# featherFet2.net
KiCad netlist of a schematic drawn in Altium Designer
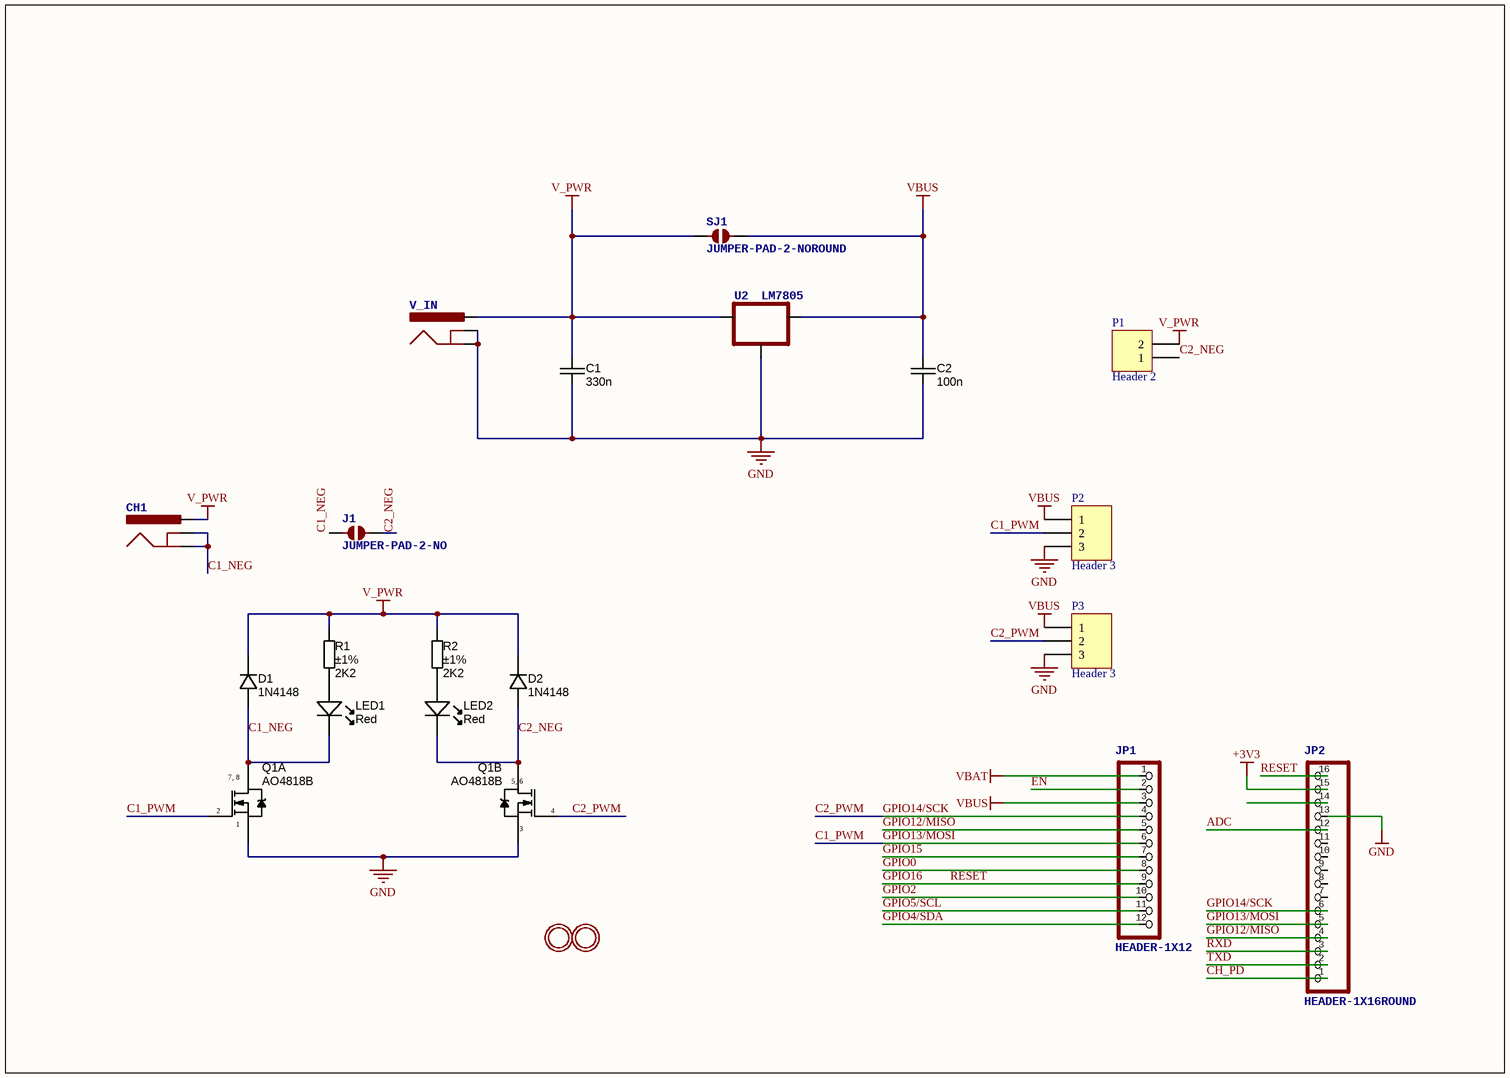
[diagram p0: featherFet2.SchDoc]

(export (version "E")
  (design (tool "Eeschema 10.0.6"))
  (components
    (comp (ref "C1")
      (value "330n")
      (footprint "CAPC2012X135N")
      (description "Capacitor SMD Cer 330nF 10% 25V X7R 0805")
      (fields (field (name "TOLERANCE") "±10%") (field (name "Comment") "approved sub OK"))
      (libsource (lib "PBL - Capacitors") (part "CAPC_330n_0805_X7R_25V_10%"))
    )
    (comp (ref "C2")
      (value "100n")
      (footprint "CAPC2012X135N")
      (description "Capacitor SMD Cer 100nF 10% 50V X7R 0805")
      (fields (field (name "TOLERANCE") "±10%") (field (name "Comment") "approved sub OK"))
      (libsource (lib "PBL - Capacitors") (part "CAPC_100n_0805_X7R_50V_10%"))
    )
    (comp (ref "CH1")
      (value "Power JackThis is the standard 5.5mm barrel jack for power. The PTH is the most common, proven, reliable, footprint. The Slot footprint only works if the mill layer is transmitted to the PCB fab house so be warned. Mating wall wart : TOL-00298 (and others)")
      (footprint "POWER_JACK_PTH")
      (libsource (lib "SparkFun-Connectors") (part "POWER_JACKPTH"))
    )
    (comp (ref "D1")
      (value "1N4148")
      (footprint "SOD523F")
      (description "Diode SMD small signal 0.2A SOD-523F")
      (libsource (lib "PBL - Diodes") (part "DIODE_1N4148_200mA_SOD523F"))
    )
    (comp (ref "D2")
      (value "1N4148")
      (footprint "SOD523F")
      (description "Diode SMD small signal 0.2A SOD-523F")
      (libsource (lib "PBL - Diodes") (part "DIODE_1N4148_200mA_SOD523F"))
    )
    (comp (ref "J1")
      (value "JUMPER-PAD-2-NO")
      (footprint "PAD-JUMPER-2-NO_NO_SILK")
      (libsource (lib "SparkFun-Passives") (part "JUMPER-PAD-2-NO"))
    )
    (comp (ref "JP1")
      (value "HEADER-1X12")
      (footprint "1X12_ROUND")
      (fields (field (name "DRAWN") "KTOWN"))
      (libsource (lib "microbuilder") (part "HEADER-1X12"))
    )
    (comp (ref "JP2")
      (value "HEADER-1X16ROUND")
      (footprint "1X16_ROUND")
      (description "PIN HEADER")
      (fields (field (name "DRAWN") "KTOWN"))
      (libsource (lib "microbuilder") (part "HEADER-1X16ROUND"))
    )
    (comp (ref "LED1")
      (value "~")
      (footprint "LED-0805-K")
      (description "LED 0805 SMD Red 6mcd 621nm")
      (fields (field (name "COLOR") "Red"))
      (libsource (lib "PBL - Light Sources") (part "LED_SMD_Red_0805_6mcd"))
    )
    (comp (ref "LED2")
      (value "~")
      (footprint "LED-0805-K")
      (description "LED 0805 SMD Red 6mcd 621nm")
      (fields (field (name "COLOR") "Red"))
      (libsource (lib "PBL - Light Sources") (part "LED_SMD_Red_0805_6mcd"))
    )
    (comp (ref "P1")
      (value "Header 2")
      (footprint "HDR1X2")
      (description "Header, 2-Pin")
      (fields (field (name "PUBLISHER") "Altium Limited"))
      (libsource (lib "Miscellaneous Connectors") (part "Header 2"))
    )
    (comp (ref "P2")
      (value "Header 3")
      (footprint "HDR1X3")
      (description "Header, 3-Pin")
      (fields (field (name "PUBLISHER") "Altium Limited"))
      (libsource (lib "Miscellaneous Connectors") (part "Header 3"))
    )
    (comp (ref "P3")
      (value "Header 3")
      (footprint "HDR1X3")
      (description "Header, 3-Pin")
      (fields (field (name "PUBLISHER") "Altium Limited"))
      (libsource (lib "Miscellaneous Connectors") (part "Header 3"))
    )
    (comp (ref "Q1")
      (value "MOSFET_AO4818B")
      (footprint "SOIC127P600X175-8AN")
      (description "MOSFET Dual-Channel 30V 8.5A SOIC-8 SMD")
      (fields (field (name "MANUFACTURER PART NUMBER 1") "AO4818B"))
      (libsource (lib "PBL - Transistors") (part "MOSFET_AO4818B"))
    )
    (comp (ref "R1")
      (value "2K2")
      (footprint "RESC2012X70N")
      (description "Resistor SMD chip 2.2k Ohm 0.125W 1% 0805")
      (fields (field (name "TOLERANCE") "±1%") (field (name "Comment") "Thick Film"))
      (libsource (lib "PBL - Resistors") (part "RES_2K2_0805_1%"))
    )
    (comp (ref "R2")
      (value "2K2")
      (footprint "RESC2012X70N")
      (description "Resistor SMD chip 2.2k Ohm 0.125W 1% 0805")
      (fields (field (name "TOLERANCE") "±1%") (field (name "Comment") "Thick Film"))
      (libsource (lib "PBL - Resistors") (part "RES_2K2_0805_1%"))
    )
    (comp (ref "SJ1")
      (value "JUMPER-PAD-2-NOROUND")
      (footprint "PAD-JUMPER-2-NO_YES_SILK_ROUND")
      (libsource (lib "SparkFun-Passives") (part "JUMPER-PAD-2-NOROUND"))
    )
    (comp (ref "U$31")
      (value "MOUNTINGHOLE2.5")
      (footprint "MOUNTINGHOLE_2.5_PLATED")
      (description "Mounting Hole   For #2 screws (0.086\"/2.18mm width, 0.094\"/2.4mm hole) use 2.5mm")
      (fields (field (name "DRAWN") "KTOWN"))
      (libsource (lib "microbuilder") (part "MOUNTINGHOLE2.5"))
    )
    (comp (ref "U$32")
      (value "MOUNTINGHOLE2.5")
      (footprint "MOUNTINGHOLE_2.5_PLATED")
      (description "Mounting Hole   For #2 screws (0.086\"/2.18mm width, 0.094\"/2.4mm hole) use 2.5mm")
      (fields (field (name "DRAWN") "KTOWN"))
      (libsource (lib "microbuilder") (part "MOUNTINGHOLE2.5"))
    )
    (comp (ref "U2")
      (value "LM7805")
      (footprint "TO220-IGO")
      (libsource (lib "SparkFun-PowerIC") (part "V_REG_78XXSINK"))
    )
    (comp (ref "V_IN")
      (value "Power JackThis is the standard 5.5mm barrel jack for power. The PTH is the most common, proven, reliable, footprint. The Slot footprint only works if the mill layer is transmitted to the PCB fab house so be warned. Mating wall wart : TOL-00298 (and others)")
      (footprint "POWER_JACK_PTH")
      (libsource (lib "SparkFun-Connectors") (part "POWER_JACKPTH"))
    )
  )
  (nets
    (net (code "1") (name "+3V3") (class "Default")
      (node (ref "JP2") (pin "15") (pinfunction "15_15") (pintype "passive"))
    )
    (net (code "2") (name "/ADC") (class "Default")
      (node (ref "JP2") (pin "12") (pinfunction "12_12") (pintype "passive"))
    )
    (net (code "3") (name "/C1_NEG") (class "Default")
      (node (ref "CH1") (pin "GND") (pinfunction "GND_GND") (pintype "passive"))
      (node (ref "CH1") (pin "GNDBREAK") (pinfunction "GNDBREAK_GNDBREAK") (pintype "passive"))
      (node (ref "D1") (pin "A") (pinfunction "A_A") (pintype "passive"))
      (node (ref "J1") (pin "1") (pinfunction "1_1") (pintype "passive"))
      (node (ref "LED1") (pin "K") (pinfunction "K_K") (pintype "passive"))
      (node (ref "Q1") (pin "7") (pinfunction "D_7") (pintype "passive"))
      (node (ref "Q1") (pin "8") (pinfunction "D_8") (pintype "passive"))
    )
    (net (code "4") (name "/C1_PWM") (class "Default")
      (node (ref "JP1") (pin "6") (pinfunction "6_6") (pintype "passive"))
      (node (ref "JP2") (pin "5") (pinfunction "5_5") (pintype "passive"))
      (node (ref "P2") (pin "2") (pinfunction "2_2") (pintype "passive"))
      (node (ref "Q1") (pin "2") (pinfunction "G_2") (pintype "passive"))
    )
    (net (code "5") (name "/C2_NEG") (class "Default")
      (node (ref "D2") (pin "A") (pinfunction "A_A") (pintype "passive"))
      (node (ref "J1") (pin "2") (pinfunction "2_2") (pintype "passive"))
      (node (ref "LED2") (pin "K") (pinfunction "K_K") (pintype "passive"))
      (node (ref "P1") (pin "1") (pinfunction "1_1") (pintype "passive"))
      (node (ref "Q1") (pin "5") (pinfunction "D_5") (pintype "passive"))
      (node (ref "Q1") (pin "6") (pinfunction "D_6") (pintype "passive"))
    )
    (net (code "6") (name "/C2_PWM") (class "Default")
      (node (ref "JP1") (pin "4") (pinfunction "4_4") (pintype "passive"))
      (node (ref "JP2") (pin "6") (pinfunction "6_6") (pintype "passive"))
      (node (ref "P3") (pin "2") (pinfunction "2_2") (pintype "passive"))
      (node (ref "Q1") (pin "4") (pinfunction "G_4") (pintype "passive"))
    )
    (net (code "7") (name "/CH_PD") (class "Default")
      (node (ref "JP2") (pin "1") (pinfunction "1_1") (pintype "passive"))
    )
    (net (code "8") (name "/EN") (class "Default")
      (node (ref "JP1") (pin "2") (pinfunction "2_2") (pintype "passive"))
    )
    (net (code "9") (name "/GPIO0") (class "Default")
      (node (ref "JP1") (pin "8") (pinfunction "8_8") (pintype "passive"))
    )
    (net (code "10") (name "/GPIO2") (class "Default")
      (node (ref "JP1") (pin "10") (pinfunction "10_10") (pintype "passive"))
    )
    (net (code "11") (name "/GPIO4{slash}SDA") (class "Default")
      (node (ref "JP1") (pin "12") (pinfunction "12_12") (pintype "passive"))
    )
    (net (code "12") (name "/GPIO5{slash}SCL") (class "Default")
      (node (ref "JP1") (pin "11") (pinfunction "11_11") (pintype "passive"))
    )
    (net (code "13") (name "/GPIO12{slash}MISO") (class "Default")
      (node (ref "JP1") (pin "5") (pinfunction "5_5") (pintype "passive"))
      (node (ref "JP2") (pin "4") (pinfunction "4_4") (pintype "passive"))
    )
    (net (code "14") (name "/GPIO15") (class "Default")
      (node (ref "JP1") (pin "7") (pinfunction "7_7") (pintype "passive"))
    )
    (net (code "15") (name "/GPIO16") (class "Default")
      (node (ref "JP1") (pin "9") (pinfunction "9_9") (pintype "passive"))
      (node (ref "JP2") (pin "16") (pinfunction "16_16") (pintype "passive"))
    )
    (net (code "16") (name "/RXD") (class "Default")
      (node (ref "JP2") (pin "3") (pinfunction "3_3") (pintype "passive"))
    )
    (net (code "17") (name "/TXD") (class "Default")
      (node (ref "JP2") (pin "2") (pinfunction "2_2") (pintype "passive"))
    )
    (net (code "18") (name "GND") (class "Default")
      (node (ref "C1") (pin "2") (pintype "passive"))
      (node (ref "C2") (pin "2") (pintype "passive"))
      (node (ref "JP2") (pin "13") (pinfunction "13_13") (pintype "passive"))
      (node (ref "P2") (pin "3") (pinfunction "3_3") (pintype "passive"))
      (node (ref "P3") (pin "3") (pinfunction "3_3") (pintype "passive"))
      (node (ref "Q1") (pin "1") (pinfunction "S_1") (pintype "passive"))
      (node (ref "Q1") (pin "3") (pinfunction "S_3") (pintype "passive"))
      (node (ref "U2") (pin "GND") (pinfunction "GND_GND") (pintype "passive"))
      (node (ref "V_IN") (pin "GND") (pinfunction "GND_GND") (pintype "passive"))
      (node (ref "V_IN") (pin "GNDBREAK") (pinfunction "GNDBREAK_GNDBREAK") (pintype "passive"))
    )
    (net (code "19") (name "Net-(LED1-PadA)") (class "Default")
      (node (ref "LED1") (pin "A") (pinfunction "A_A") (pintype "passive"))
      (node (ref "R1") (pin "2") (pinfunction "2_2") (pintype "passive"))
    )
    (net (code "20") (name "Net-(LED2-PadA)") (class "Default")
      (node (ref "LED2") (pin "A") (pinfunction "A_A") (pintype "passive"))
      (node (ref "R2") (pin "2") (pinfunction "2_2") (pintype "passive"))
    )
    (net (code "21") (name "VBAT") (class "Default")
      (node (ref "JP1") (pin "1") (pinfunction "1_1") (pintype "passive"))
    )
    (net (code "22") (name "VBUS") (class "Default")
      (node (ref "C2") (pin "1") (pintype "passive"))
      (node (ref "JP1") (pin "3") (pinfunction "3_3") (pintype "passive"))
      (node (ref "P2") (pin "1") (pinfunction "1_1") (pintype "passive"))
      (node (ref "P3") (pin "1") (pinfunction "1_1") (pintype "passive"))
      (node (ref "SJ1") (pin "2") (pinfunction "2_2") (pintype "passive"))
      (node (ref "U2") (pin "OUT") (pinfunction "OUT_OUT") (pintype "passive"))
    )
    (net (code "23") (name "V_PWR") (class "Default")
      (node (ref "C1") (pin "1") (pintype "passive"))
      (node (ref "CH1") (pin "PWR") (pinfunction "PWR_PWR") (pintype "passive"))
      (node (ref "D1") (pin "K") (pinfunction "K_K") (pintype "passive"))
      (node (ref "D2") (pin "K") (pinfunction "K_K") (pintype "passive"))
      (node (ref "P1") (pin "2") (pinfunction "2_2") (pintype "passive"))
      (node (ref "R1") (pin "1") (pinfunction "1_1") (pintype "passive"))
      (node (ref "R2") (pin "1") (pinfunction "1_1") (pintype "passive"))
      (node (ref "SJ1") (pin "1") (pinfunction "1_1") (pintype "passive"))
      (node (ref "U2") (pin "IN") (pinfunction "IN_IN") (pintype "passive"))
      (node (ref "V_IN") (pin "PWR") (pinfunction "PWR_PWR") (pintype "passive"))
    )
    (net (code "24") (name "unconnected-(JP2-Pad7)") (class "Default")
      (node (ref "JP2") (pin "7") (pinfunction "7_7") (pintype "passive"))
    )
    (net (code "25") (name "unconnected-(JP2-Pad8)") (class "Default")
      (node (ref "JP2") (pin "8") (pinfunction "8_8") (pintype "passive"))
    )
    (net (code "26") (name "unconnected-(JP2-Pad9)") (class "Default")
      (node (ref "JP2") (pin "9") (pinfunction "9_9") (pintype "passive"))
    )
    (net (code "27") (name "unconnected-(JP2-Pad10)") (class "Default")
      (node (ref "JP2") (pin "10") (pinfunction "10_10") (pintype "passive"))
    )
    (net (code "28") (name "unconnected-(JP2-Pad11)") (class "Default")
      (node (ref "JP2") (pin "11") (pinfunction "11_11") (pintype "passive"))
    )
    (net (code "29") (name "unconnected-(JP2-Pad14)") (class "Default")
      (node (ref "JP2") (pin "14") (pinfunction "14_14") (pintype "passive"))
    )
  )
)
